# opemGBZ.net
KiCad netlist of a schematic drawn in EAGLE
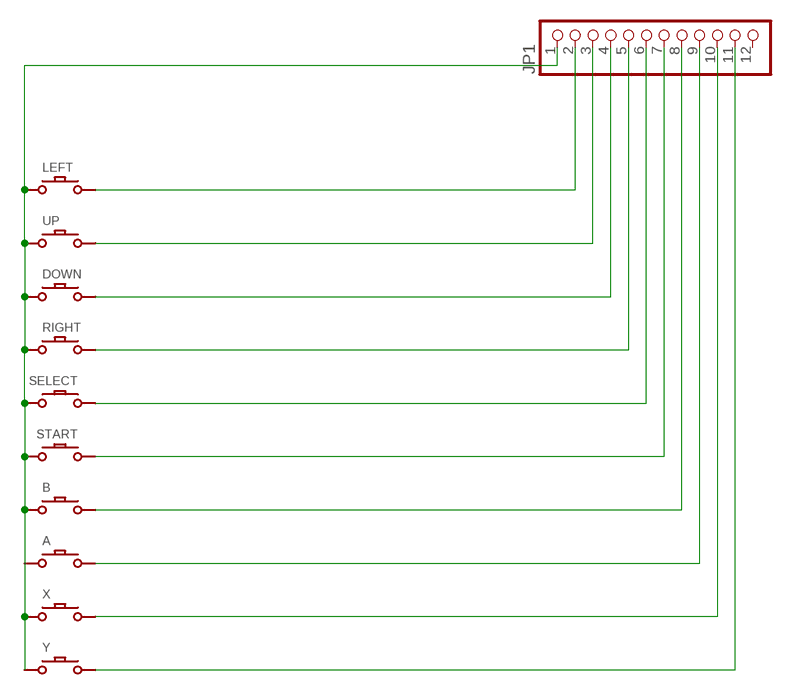
[diagram p0: schematic, sheet 1]

(export (version "E")
  (design (tool "Eeschema 10.0.6"))
  (components
    (comp (ref "A")
      (value "DMG-BTN")
      (footprint "eagle-import:DMG-BTN")
      (libsource (lib "eagle-import") (part "DMG-BTNREGULAR"))
    )
    (comp (ref "B")
      (value "DMG-BTN")
      (footprint "eagle-import:DMG-BTN")
      (libsource (lib "eagle-import") (part "DMG-BTNREGULAR"))
    )
    (comp (ref "DOWN")
      (value "DMG-BTN")
      (footprint "eagle-import:DMG-BTN")
      (libsource (lib "eagle-import") (part "DMG-BTNREGULAR"))
    )
    (comp (ref "JP1")
      (value "PINHD-1X12")
      (footprint "eagle-import:1X12")
      (libsource (lib "eagle-import") (part "PINHD-1X12"))
    )
    (comp (ref "LEFT")
      (value "DMG-BTN")
      (footprint "eagle-import:DMG-BTN")
      (libsource (lib "eagle-import") (part "DMG-BTNREGULAR"))
    )
    (comp (ref "RIGHT")
      (value "DMG-BTN")
      (footprint "eagle-import:DMG-BTN")
      (libsource (lib "eagle-import") (part "DMG-BTNREGULAR"))
    )
    (comp (ref "SELECT")
      (value "DMG-BTN")
      (footprint "eagle-import:DMG-SEL")
      (libsource (lib "eagle-import") (part "DMG-BTNSELECT"))
    )
    (comp (ref "START")
      (value "DMG-BTN")
      (footprint "eagle-import:DMG-SEL")
      (libsource (lib "eagle-import") (part "DMG-BTNSELECT"))
    )
    (comp (ref "UP")
      (value "DMG-BTN")
      (footprint "eagle-import:DMG-BTN")
      (libsource (lib "eagle-import") (part "DMG-BTNREGULAR"))
    )
    (comp (ref "X")
      (value "DMG-BTN")
      (footprint "eagle-import:DMG-BTN")
      (libsource (lib "eagle-import") (part "DMG-BTNREGULAR"))
    )
    (comp (ref "Y")
      (value "DMG-BTN")
      (footprint "eagle-import:DMG-BTN")
      (libsource (lib "eagle-import") (part "DMG-BTNREGULAR"))
    )
  )
  (nets
    (net (code "1") (name "Net-(A-PadP$1)") (class "Default")
      (node (ref "A") (pin "P$1") (pinfunction "P$1_P$1") (pintype "bidirectional"))
      (node (ref "B") (pin "P$1") (pinfunction "P$1_P$1") (pintype "bidirectional"))
      (node (ref "DOWN") (pin "P$1") (pinfunction "P$1_P$1") (pintype "bidirectional"))
      (node (ref "JP1") (pin "1") (pinfunction "1_1") (pintype "passive"))
      (node (ref "LEFT") (pin "P$1") (pinfunction "P$1_P$1") (pintype "bidirectional"))
      (node (ref "RIGHT") (pin "P$1") (pinfunction "P$1_P$1") (pintype "bidirectional"))
      (node (ref "SELECT") (pin "P$2") (pinfunction "P$2_P$2") (pintype "bidirectional"))
      (node (ref "START") (pin "P$2") (pinfunction "P$2_P$2") (pintype "bidirectional"))
      (node (ref "UP") (pin "P$1") (pinfunction "P$1_P$1") (pintype "bidirectional"))
      (node (ref "X") (pin "P$1") (pinfunction "P$1_P$1") (pintype "bidirectional"))
      (node (ref "Y") (pin "P$1") (pinfunction "P$1_P$1") (pintype "bidirectional"))
    )
    (net (code "2") (name "Net-(A-PadP$2)") (class "Default")
      (node (ref "A") (pin "P$2") (pinfunction "P$2_P$2") (pintype "bidirectional"))
      (node (ref "JP1") (pin "9") (pinfunction "9_9") (pintype "passive"))
    )
    (net (code "3") (name "Net-(B-PadP$2)") (class "Default")
      (node (ref "B") (pin "P$2") (pinfunction "P$2_P$2") (pintype "bidirectional"))
      (node (ref "JP1") (pin "8") (pinfunction "8_8") (pintype "passive"))
    )
    (net (code "4") (name "Net-(DOWN-PadP$2)") (class "Default")
      (node (ref "DOWN") (pin "P$2") (pinfunction "P$2_P$2") (pintype "bidirectional"))
      (node (ref "JP1") (pin "4") (pinfunction "4_4") (pintype "passive"))
    )
    (net (code "5") (name "Net-(JP1-Pad2)") (class "Default")
      (node (ref "JP1") (pin "2") (pinfunction "2_2") (pintype "passive"))
      (node (ref "LEFT") (pin "P$2") (pinfunction "P$2_P$2") (pintype "bidirectional"))
    )
    (net (code "6") (name "Net-(JP1-Pad3)") (class "Default")
      (node (ref "JP1") (pin "3") (pinfunction "3_3") (pintype "passive"))
      (node (ref "UP") (pin "P$2") (pinfunction "P$2_P$2") (pintype "bidirectional"))
    )
    (net (code "7") (name "Net-(JP1-Pad5)") (class "Default")
      (node (ref "JP1") (pin "5") (pinfunction "5_5") (pintype "passive"))
      (node (ref "RIGHT") (pin "P$2") (pinfunction "P$2_P$2") (pintype "bidirectional"))
    )
    (net (code "8") (name "Net-(JP1-Pad6)") (class "Default")
      (node (ref "JP1") (pin "6") (pinfunction "6_6") (pintype "passive"))
      (node (ref "SELECT") (pin "P$1") (pinfunction "P$1_P$1") (pintype "bidirectional"))
    )
    (net (code "9") (name "Net-(JP1-Pad7)") (class "Default")
      (node (ref "JP1") (pin "7") (pinfunction "7_7") (pintype "passive"))
      (node (ref "START") (pin "P$1") (pinfunction "P$1_P$1") (pintype "bidirectional"))
    )
    (net (code "10") (name "Net-(JP1-Pad10)") (class "Default")
      (node (ref "JP1") (pin "10") (pinfunction "10_10") (pintype "passive"))
      (node (ref "X") (pin "P$2") (pinfunction "P$2_P$2") (pintype "bidirectional"))
    )
    (net (code "11") (name "Net-(JP1-Pad11)") (class "Default")
      (node (ref "JP1") (pin "11") (pinfunction "11_11") (pintype "passive"))
      (node (ref "Y") (pin "P$2") (pinfunction "P$2_P$2") (pintype "bidirectional"))
    )
    (net (code "12") (name "unconnected-(JP1-Pad12)") (class "Default")
      (node (ref "JP1") (pin "12") (pinfunction "12_12") (pintype "passive"))
    )
  )
)
